# SCH_lucid_vr_proto_5_pcbs_2023-09-04.net
KiCad netlist of a schematic drawn in EasyEDA
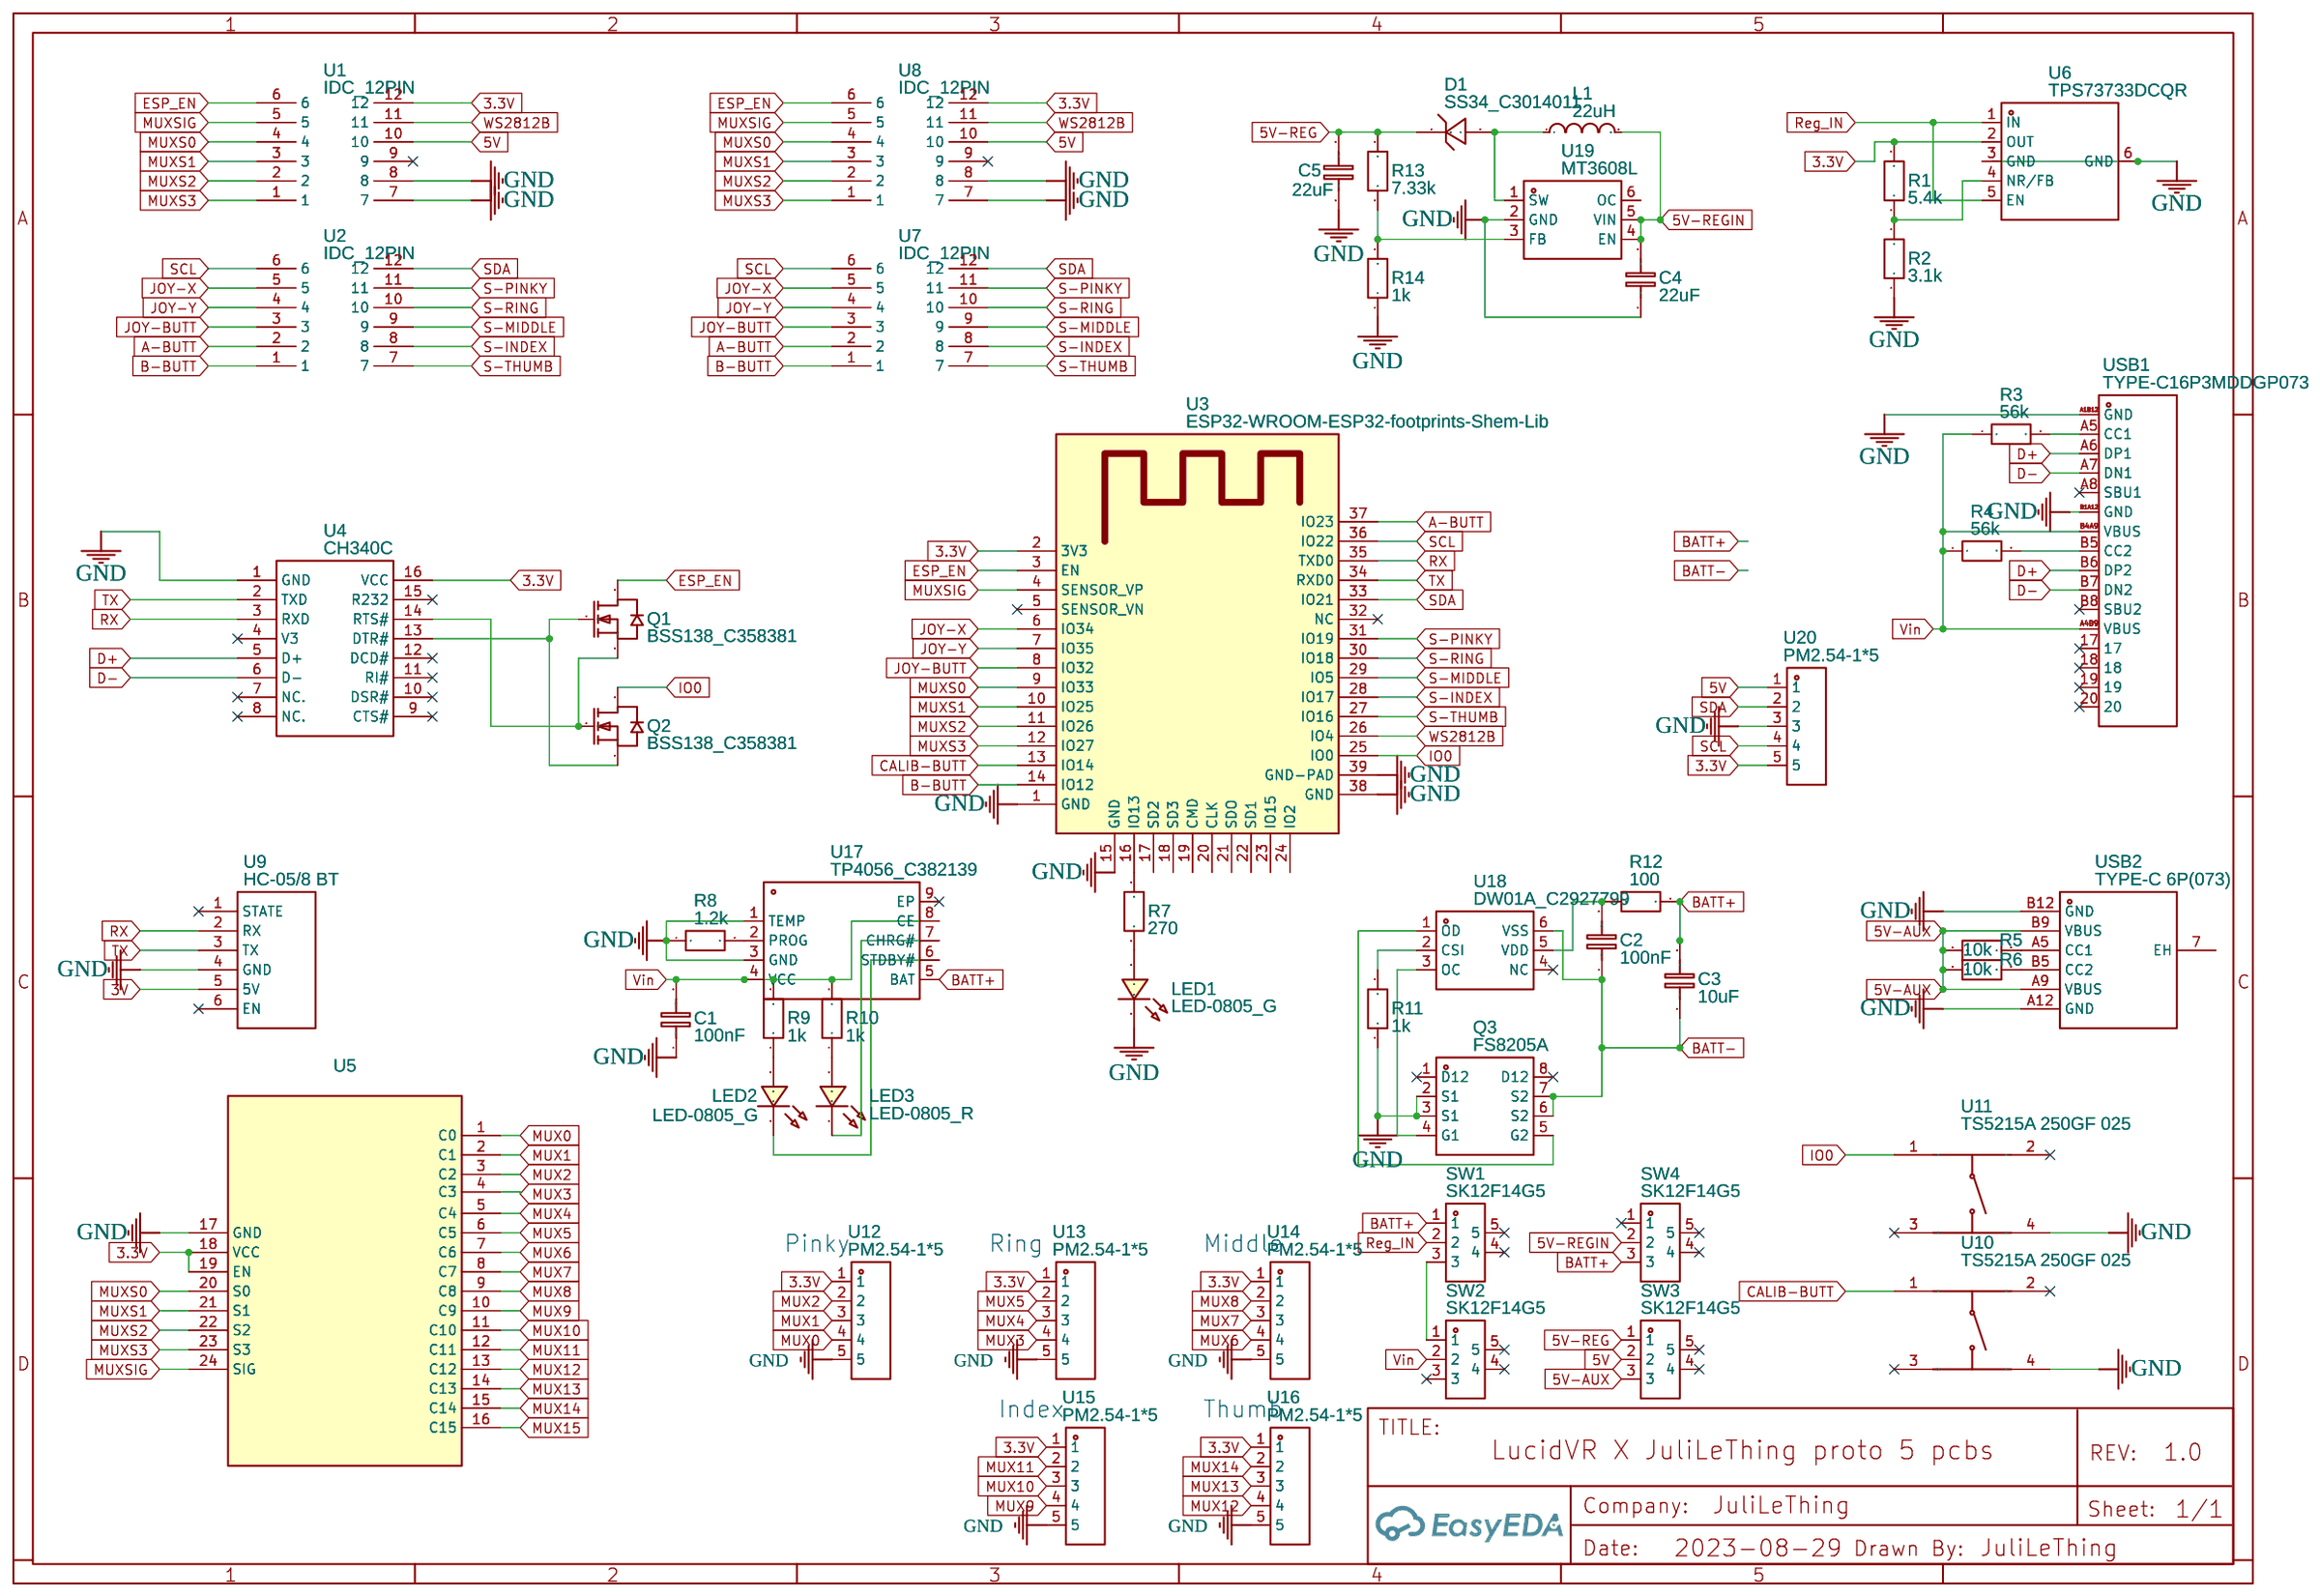
[diagram p0: schematic sheet]

(export (version "E")
  (design (tool "Eeschema 10.0.6"))
  (components
    (comp (ref "C1") (value "100nF") (libsource (lib "") (part "C_1206_EU_1")))
    (comp (ref "C2") (value "100nF") (libsource (lib "") (part "C_1206_EU_2")))
    (comp (ref "C3") (value "10uF") (libsource (lib "") (part "C_1206_EU_2")))
    (comp (ref "C4") (value "22uF") (libsource (lib "") (part "C_1206_EU")))
    (comp (ref "C5") (value "22uF") (libsource (lib "") (part "C_1206_EU")))
    (comp (ref "D1")
      (value "SS34_C3014011")
      (fields (field (name "Manufacturer Part") "SS34") (field (name "Manufacturer") "FOSAN(富信)"))
      (libsource (lib "") (part "SS34_C3014011"))
    )
    (comp (ref "L1") (value "22uH") (libsource (lib "") (part "L0805_US")))
    (comp (ref "LED1")
      (value "LED-0805_G")
      (fields (field (name "Manufacturer Part") "NCD0805G1") (field (name "Manufacturer") "国星光电"))
      (libsource (lib "") (part "LED-0805_G"))
    )
    (comp (ref "LED2")
      (value "LED-0805_G")
      (fields (field (name "Manufacturer Part") "NCD0805G1") (field (name "Manufacturer") "国星光电"))
      (libsource (lib "") (part "LED-0805_G"))
    )
    (comp (ref "LED3")
      (value "LED-0805_R")
      (fields
        (field (name "Manufacturer Part") "17-21SURC/S530-A3/TR8")
        (field (name "Manufacturer") "EVERLIGHT(台湾亿光)")
      )
      (libsource (lib "") (part "LED-0805_R"))
    )
    (comp (ref "Q1")
      (value "BSS138_C358381")
      (fields (field (name "Manufacturer Part") "BSS138") (field (name "Manufacturer") "BLUE ROCKET(蓝箭)"))
      (libsource (lib "") (part "BSS138_C358381"))
    )
    (comp (ref "Q2")
      (value "BSS138_C358381")
      (fields (field (name "Manufacturer Part") "BSS138") (field (name "Manufacturer") "BLUE ROCKET(蓝箭)"))
      (libsource (lib "") (part "BSS138_C358381"))
    )
    (comp (ref "Q3")
      (value "FS8205A")
      (fields (field (name "Manufacturer") "FORTUNE(富晶)"))
      (libsource (lib "") (part "FS8205A"))
    )
    (comp (ref "R1") (value "5.4k") (libsource (lib "") (part "R_1206_EU")))
    (comp (ref "R2") (value "3.1k") (libsource (lib "") (part "R_1206_EU")))
    (comp (ref "R3") (value "56k") (libsource (lib "") (part "R_1206_EU_1")))
    (comp (ref "R4") (value "56k") (libsource (lib "") (part "R_1206_EU_1")))
    (comp (ref "R5") (value "10k") (libsource (lib "") (part "R_1206_EU_1")))
    (comp (ref "R6") (value "10k") (libsource (lib "") (part "R_1206_EU_1")))
    (comp (ref "R7") (value "270") (libsource (lib "") (part "R_1206_EU_2")))
    (comp (ref "R8") (value "1.2k") (libsource (lib "") (part "R_1206_EU_1")))
    (comp (ref "R9") (value "1k") (libsource (lib "") (part "R_1206_EU")))
    (comp (ref "R10") (value "1k") (libsource (lib "") (part "R_1206_EU")))
    (comp (ref "R11") (value "1k") (libsource (lib "") (part "R_1206_EU")))
    (comp (ref "R12") (value "100") (libsource (lib "") (part "R_1206_EU_1")))
    (comp (ref "R13") (value "7.33k") (libsource (lib "") (part "R_1206_EU")))
    (comp (ref "R14") (value "1k") (libsource (lib "") (part "R_1206_EU")))
    (comp (ref "SW1")
      (value "SK12F14G5")
      (fields (field (name "Manufacturer") "SHOU HAN(首韩)"))
      (libsource (lib "") (part "SK12F14G5"))
    )
    (comp (ref "SW2")
      (value "SK12F14G5")
      (fields (field (name "Manufacturer") "SHOU HAN(首韩)"))
      (libsource (lib "") (part "SK12F14G5"))
    )
    (comp (ref "SW3")
      (value "SK12F14G5")
      (fields (field (name "Manufacturer") "SHOU HAN(首韩)"))
      (libsource (lib "") (part "SK12F14G5"))
    )
    (comp (ref "SW4")
      (value "SK12F14G5")
      (fields (field (name "Manufacturer") "SHOU HAN(首韩)"))
      (libsource (lib "") (part "SK12F14G5"))
    )
    (comp (ref "U1") (value "IDC_12PIN") (libsource (lib "") (part "IDC_12PIN")))
    (comp (ref "U2") (value "IDC_12PIN") (libsource (lib "") (part "IDC_12PIN")))
    (comp (ref "U3")
      (value "ESP32-WROOM-ESP32-footprints-Shem-Lib")
      (libsource (lib "") (part "ESP32-WROOM-ESP32-footprints-Shem-Lib"))
    )
    (comp (ref "U4")
      (value "CH340C")
      (fields (field (name "Manufacturer") "WCH(南京沁恒)"))
      (libsource (lib "") (part "CH340C"))
    )
    (comp (ref "U5") (value "NO") (libsource (lib "") (part "16x1_Mux_board_CD74HC4067")))
    (comp (ref "U6")
      (value "TPS73733DCQR")
      (fields (field (name "Manufacturer") "TI(德州仪器)"))
      (libsource (lib "") (part "TPS73733DCQR"))
    )
    (comp (ref "U7") (value "IDC_12PIN") (libsource (lib "") (part "IDC_12PIN")))
    (comp (ref "U8") (value "IDC_12PIN") (libsource (lib "") (part "IDC_12PIN")))
    (comp (ref "U9") (value "HC-05/8 BT") (libsource (lib "") (part "HC08 Bluetooth Module")))
    (comp (ref "U10")
      (value "TS5215A 250GF 025")
      (fields
        (field (name "Manufacturer Part") "TS5215A 250gf 025")
        (field (name "Manufacturer") "SHOU HAN(首韩)")
      )
      (libsource (lib "") (part "TS5215A 250GF 025"))
    )
    (comp (ref "U11")
      (value "TS5215A 250GF 025")
      (fields
        (field (name "Manufacturer Part") "TS5215A 250gf 025")
        (field (name "Manufacturer") "SHOU HAN(首韩)")
      )
      (libsource (lib "") (part "TS5215A 250GF 025"))
    )
    (comp (ref "U12")
      (value "PM2.54-1*5")
      (fields (field (name "Manufacturer") "ZHOURI(洲日)"))
      (libsource (lib "") (part "PM2.54-1*5"))
    )
    (comp (ref "U13")
      (value "PM2.54-1*5")
      (fields (field (name "Manufacturer") "ZHOURI(洲日)"))
      (libsource (lib "") (part "PM2.54-1*5"))
    )
    (comp (ref "U14")
      (value "PM2.54-1*5")
      (fields (field (name "Manufacturer") "ZHOURI(洲日)"))
      (libsource (lib "") (part "PM2.54-1*5"))
    )
    (comp (ref "U15")
      (value "PM2.54-1*5")
      (fields (field (name "Manufacturer") "ZHOURI(洲日)"))
      (libsource (lib "") (part "PM2.54-1*5"))
    )
    (comp (ref "U16")
      (value "PM2.54-1*5")
      (fields (field (name "Manufacturer") "ZHOURI(洲日)"))
      (libsource (lib "") (part "PM2.54-1*5"))
    )
    (comp (ref "U17")
      (value "TP4056_C382139")
      (fields (field (name "Manufacturer Part") "TP4056") (field (name "Manufacturer") "TPOWER(天源)"))
      (libsource (lib "") (part "TP4056_C382139"))
    )
    (comp (ref "U18")
      (value "DW01A_C2927799")
      (fields (field (name "Manufacturer Part") "DW01A") (field (name "Manufacturer") "YONGYUTAI(永裕泰)"))
      (libsource (lib "") (part "DW01A_C2927799"))
    )
    (comp (ref "U19")
      (value "MT3608L")
      (fields (field (name "Manufacturer") "西安航天民芯"))
      (libsource (lib "") (part "MT3608L"))
    )
    (comp (ref "U20")
      (value "PM2.54-1*5")
      (fields (field (name "Manufacturer") "ZHOURI(洲日)"))
      (libsource (lib "") (part "PM2.54-1*5"))
    )
    (comp (ref "USB1")
      (value "TYPE-C16P3MDDGP073")
      (fields (field (name "Manufacturer") "SHOU HAN(首韩)"))
      (libsource (lib "") (part "TYPE-C16P3MDDGP073"))
    )
    (comp (ref "USB2")
      (value "TYPE-C 6P(073)")
      (fields (field (name "Manufacturer") "SHOU HAN(首韩)"))
      (libsource (lib "") (part "TYPE-C 6P(073)"))
    )
  )
  (nets
    (net (code "1") (name "3.3V") (class "Default")
      (node (ref "R1") (pin "2") (pinfunction "2_2") (pintype "unspecified"))
      (node (ref "U1") (pin "12") (pinfunction "12_12") (pintype "unspecified"))
      (node (ref "U12") (pin "1") (pinfunction "1_1") (pintype "unspecified"))
      (node (ref "U13") (pin "1") (pinfunction "1_1") (pintype "unspecified"))
      (node (ref "U14") (pin "1") (pinfunction "1_1") (pintype "unspecified"))
      (node (ref "U15") (pin "1") (pinfunction "1_1") (pintype "unspecified"))
      (node (ref "U16") (pin "1") (pinfunction "1_1") (pintype "unspecified"))
      (node (ref "U20") (pin "5") (pinfunction "5_5") (pintype "unspecified"))
      (node (ref "U3") (pin "2") (pinfunction "3V3_2") (pintype "bidirectional"))
      (node (ref "U4") (pin "16") (pinfunction "VCC_16") (pintype "unspecified"))
      (node (ref "U5") (pin "18") (pinfunction "VCC_18") (pintype "unspecified"))
      (node (ref "U5") (pin "19") (pinfunction "EN_19") (pintype "unspecified"))
      (node (ref "U6") (pin "2") (pinfunction "OUT_2") (pintype "unspecified"))
      (node (ref "U8") (pin "12") (pinfunction "12_12") (pintype "unspecified"))
    )
    (net (code "2") (name "3V") (class "Default")
      (node (ref "U9") (pin "5") (pinfunction "5V_5") (pintype "unspecified"))
    )
    (net (code "3") (name "5V") (class "Default")
      (node (ref "SW3") (pin "2") (pinfunction "2_2") (pintype "unspecified"))
      (node (ref "U1") (pin "10") (pinfunction "10_10") (pintype "unspecified"))
      (node (ref "U20") (pin "1") (pinfunction "1_1") (pintype "unspecified"))
      (node (ref "U8") (pin "10") (pinfunction "10_10") (pintype "unspecified"))
    )
    (net (code "4") (name "5V-AUX") (class "Default")
      (node (ref "R5") (pin "1") (pinfunction "1_1") (pintype "unspecified"))
      (node (ref "R6") (pin "1") (pinfunction "1_1") (pintype "unspecified"))
      (node (ref "SW3") (pin "3") (pinfunction "3_3") (pintype "unspecified"))
      (node (ref "USB2") (pin "A9") (pinfunction "VBUS_A9") (pintype "unspecified"))
      (node (ref "USB2") (pin "B9") (pinfunction "VBUS_B9") (pintype "unspecified"))
    )
    (net (code "5") (name "5V-REG") (class "Default")
      (node (ref "C5") (pin "2") (pinfunction "2_2") (pintype "unspecified"))
      (node (ref "D1") (pin "1") (pinfunction "C_1") (pintype "unspecified"))
      (node (ref "R13") (pin "2") (pinfunction "2_2") (pintype "unspecified"))
      (node (ref "SW3") (pin "1") (pinfunction "1_1") (pintype "unspecified"))
    )
    (net (code "6") (name "5V-REGIN") (class "Default")
      (node (ref "C4") (pin "2") (pinfunction "2_2") (pintype "unspecified"))
      (node (ref "L1") (pin "2") (pinfunction "2_2") (pintype "unspecified"))
      (node (ref "SW4") (pin "2") (pinfunction "2_2") (pintype "unspecified"))
      (node (ref "U19") (pin "4") (pinfunction "EN_4") (pintype "unspecified"))
      (node (ref "U19") (pin "5") (pinfunction "VIN_5") (pintype "unspecified"))
    )
    (net (code "7") (name "A-BUTT") (class "Default")
      (node (ref "U2") (pin "2") (pinfunction "2_2") (pintype "unspecified"))
      (node (ref "U3") (pin "37") (pinfunction "IO23_37") (pintype "bidirectional"))
      (node (ref "U7") (pin "2") (pinfunction "2_2") (pintype "unspecified"))
    )
    (net (code "8") (name "B-BUTT") (class "Default")
      (node (ref "U2") (pin "1") (pinfunction "1_1") (pintype "unspecified"))
      (node (ref "U3") (pin "14") (pinfunction "IO12_14") (pintype "bidirectional"))
      (node (ref "U7") (pin "1") (pinfunction "1_1") (pintype "unspecified"))
    )
    (net (code "9") (name "BATT+") (class "Default")
      (node (ref "C3") (pin "2") (pinfunction "2_2") (pintype "unspecified"))
      (node (ref "R12") (pin "2") (pinfunction "2_2") (pintype "unspecified"))
      (node (ref "SW1") (pin "1") (pinfunction "1_1") (pintype "unspecified"))
      (node (ref "SW4") (pin "3") (pinfunction "3_3") (pintype "unspecified"))
      (node (ref "U17") (pin "5") (pinfunction "BAT_5") (pintype "unspecified"))
    )
    (net (code "10") (name "BATT-") (class "Default")
      (node (ref "C2") (pin "1") (pinfunction "1_1") (pintype "unspecified"))
      (node (ref "C3") (pin "1") (pinfunction "1_1") (pintype "unspecified"))
      (node (ref "Q3") (pin "6") (pinfunction "S2_6") (pintype "unspecified"))
      (node (ref "Q3") (pin "7") (pinfunction "S2_7") (pintype "unspecified"))
      (node (ref "U18") (pin "6") (pinfunction "VSS_6") (pintype "unspecified"))
    )
    (net (code "11") (name "CALIB-BUTT") (class "Default")
      (node (ref "U10") (pin "1") (pinfunction "1_1") (pintype "unspecified"))
      (node (ref "U3") (pin "13") (pinfunction "IO14_13") (pintype "bidirectional"))
    )
    (net (code "12") (name "D+") (class "Default")
      (node (ref "U4") (pin "5") (pinfunction "D+_5") (pintype "unspecified"))
      (node (ref "USB1") (pin "A6") (pinfunction "DP1_A6") (pintype "unspecified"))
      (node (ref "USB1") (pin "B6") (pinfunction "DP2_B6") (pintype "unspecified"))
    )
    (net (code "13") (name "D-") (class "Default")
      (node (ref "U4") (pin "6") (pinfunction "D-_6") (pintype "unspecified"))
      (node (ref "USB1") (pin "A7") (pinfunction "DN1_A7") (pintype "unspecified"))
      (node (ref "USB1") (pin "B7") (pinfunction "DN2_B7") (pintype "unspecified"))
    )
    (net (code "14") (name "ESP_EN") (class "Default")
      (node (ref "Q1") (pin "3") (pinfunction "D_3") (pintype "unspecified"))
      (node (ref "U1") (pin "6") (pinfunction "6_6") (pintype "unspecified"))
      (node (ref "U3") (pin "3") (pinfunction "EN_3") (pintype "input"))
      (node (ref "U8") (pin "6") (pinfunction "6_6") (pintype "unspecified"))
    )
    (net (code "15") (name "GND") (class "Default")
      (node (ref "C1") (pin "1") (pinfunction "1_1") (pintype "unspecified"))
      (node (ref "C4") (pin "1") (pinfunction "1_1") (pintype "unspecified"))
      (node (ref "C5") (pin "1") (pinfunction "1_1") (pintype "unspecified"))
      (node (ref "LED1") (pin "2") (pinfunction "2_2") (pintype "unspecified"))
      (node (ref "Q3") (pin "2") (pinfunction "S1_2") (pintype "unspecified"))
      (node (ref "Q3") (pin "3") (pinfunction "S1_3") (pintype "unspecified"))
      (node (ref "R11") (pin "1") (pinfunction "1_1") (pintype "unspecified"))
      (node (ref "R14") (pin "1") (pinfunction "1_1") (pintype "unspecified"))
      (node (ref "R2") (pin "1") (pinfunction "1_1") (pintype "unspecified"))
      (node (ref "R8") (pin "1") (pinfunction "1_1") (pintype "unspecified"))
      (node (ref "U1") (pin "7") (pinfunction "7_7") (pintype "unspecified"))
      (node (ref "U1") (pin "8") (pinfunction "8_8") (pintype "unspecified"))
      (node (ref "U10") (pin "4") (pinfunction "4_4") (pintype "unspecified"))
      (node (ref "U11") (pin "4") (pinfunction "4_4") (pintype "unspecified"))
      (node (ref "U12") (pin "5") (pinfunction "5_5") (pintype "unspecified"))
      (node (ref "U13") (pin "5") (pinfunction "5_5") (pintype "unspecified"))
      (node (ref "U14") (pin "5") (pinfunction "5_5") (pintype "unspecified"))
      (node (ref "U15") (pin "5") (pinfunction "5_5") (pintype "unspecified"))
      (node (ref "U16") (pin "5") (pinfunction "5_5") (pintype "unspecified"))
      (node (ref "U17") (pin "1") (pinfunction "TEMP_1") (pintype "unspecified"))
      (node (ref "U17") (pin "3") (pinfunction "GND_3") (pintype "unspecified"))
      (node (ref "U19") (pin "2") (pinfunction "GND_2") (pintype "unspecified"))
      (node (ref "U20") (pin "3") (pinfunction "3_3") (pintype "unspecified"))
      (node (ref "U3") (pin "1") (pinfunction "GND_1") (pintype "bidirectional"))
      (node (ref "U3") (pin "15") (pinfunction "GND_15") (pintype "bidirectional"))
      (node (ref "U3") (pin "38") (pinfunction "GND_38") (pintype "bidirectional"))
      (node (ref "U3") (pin "39") (pinfunction "GND-PAD_39") (pintype "bidirectional"))
      (node (ref "U4") (pin "1") (pinfunction "GND_1") (pintype "unspecified"))
      (node (ref "U5") (pin "17") (pinfunction "GND_17") (pintype "unspecified"))
      (node (ref "U6") (pin "6") (pinfunction "GND_6") (pintype "unspecified"))
      (node (ref "U8") (pin "7") (pinfunction "7_7") (pintype "unspecified"))
      (node (ref "U8") (pin "8") (pinfunction "8_8") (pintype "unspecified"))
      (node (ref "U9") (pin "4") (pinfunction "GND_4") (pintype "unspecified"))
      (node (ref "USB1") (pin "A1B12") (pinfunction "GND_A1B12") (pintype "unspecified"))
      (node (ref "USB1") (pin "B1A12") (pinfunction "GND_B1A12") (pintype "unspecified"))
      (node (ref "USB2") (pin "A12") (pinfunction "GND_A12") (pintype "unspecified"))
      (node (ref "USB2") (pin "B12") (pinfunction "GND_B12") (pintype "unspecified"))
    )
    (net (code "16") (name "IO0") (class "Default")
      (node (ref "Q2") (pin "3") (pinfunction "D_3") (pintype "unspecified"))
      (node (ref "U11") (pin "1") (pinfunction "1_1") (pintype "unspecified"))
      (node (ref "U3") (pin "25") (pinfunction "IO0_25") (pintype "bidirectional"))
    )
    (net (code "17") (name "JOY-BUTT") (class "Default")
      (node (ref "U2") (pin "3") (pinfunction "3_3") (pintype "unspecified"))
      (node (ref "U3") (pin "8") (pinfunction "IO32_8") (pintype "bidirectional"))
      (node (ref "U7") (pin "3") (pinfunction "3_3") (pintype "unspecified"))
    )
    (net (code "18") (name "JOY-X") (class "Default")
      (node (ref "U2") (pin "5") (pinfunction "5_5") (pintype "unspecified"))
      (node (ref "U3") (pin "6") (pinfunction "IO34_6") (pintype "bidirectional"))
      (node (ref "U7") (pin "5") (pinfunction "5_5") (pintype "unspecified"))
    )
    (net (code "19") (name "JOY-Y") (class "Default")
      (node (ref "U2") (pin "4") (pinfunction "4_4") (pintype "unspecified"))
      (node (ref "U3") (pin "7") (pinfunction "IO35_7") (pintype "bidirectional"))
      (node (ref "U7") (pin "4") (pinfunction "4_4") (pintype "unspecified"))
    )
    (net (code "20") (name "MUX0") (class "Default")
      (node (ref "U12") (pin "4") (pinfunction "4_4") (pintype "unspecified"))
      (node (ref "U5") (pin "1") (pinfunction "C0_1") (pintype "unspecified"))
    )
    (net (code "21") (name "MUX1") (class "Default")
      (node (ref "U12") (pin "3") (pinfunction "3_3") (pintype "unspecified"))
      (node (ref "U5") (pin "2") (pinfunction "C1_2") (pintype "unspecified"))
    )
    (net (code "22") (name "MUX2") (class "Default")
      (node (ref "U12") (pin "2") (pinfunction "2_2") (pintype "unspecified"))
      (node (ref "U5") (pin "3") (pinfunction "C2_3") (pintype "unspecified"))
    )
    (net (code "23") (name "MUX3") (class "Default")
      (node (ref "U13") (pin "4") (pinfunction "4_4") (pintype "unspecified"))
      (node (ref "U5") (pin "4") (pinfunction "C3_4") (pintype "unspecified"))
    )
    (net (code "24") (name "MUX4") (class "Default")
      (node (ref "U13") (pin "3") (pinfunction "3_3") (pintype "unspecified"))
      (node (ref "U5") (pin "5") (pinfunction "C4_5") (pintype "unspecified"))
    )
    (net (code "25") (name "MUX5") (class "Default")
      (node (ref "U13") (pin "2") (pinfunction "2_2") (pintype "unspecified"))
      (node (ref "U5") (pin "6") (pinfunction "C5_6") (pintype "unspecified"))
    )
    (net (code "26") (name "MUX6") (class "Default")
      (node (ref "U14") (pin "4") (pinfunction "4_4") (pintype "unspecified"))
      (node (ref "U5") (pin "7") (pinfunction "C6_7") (pintype "unspecified"))
    )
    (net (code "27") (name "MUX7") (class "Default")
      (node (ref "U14") (pin "3") (pinfunction "3_3") (pintype "unspecified"))
      (node (ref "U5") (pin "8") (pinfunction "C7_8") (pintype "unspecified"))
    )
    (net (code "28") (name "MUX8") (class "Default")
      (node (ref "U14") (pin "2") (pinfunction "2_2") (pintype "unspecified"))
      (node (ref "U5") (pin "9") (pinfunction "C8_9") (pintype "unspecified"))
    )
    (net (code "29") (name "MUX9") (class "Default")
      (node (ref "U15") (pin "4") (pinfunction "4_4") (pintype "unspecified"))
      (node (ref "U5") (pin "10") (pinfunction "C9_10") (pintype "unspecified"))
    )
    (net (code "30") (name "MUX10") (class "Default")
      (node (ref "U15") (pin "3") (pinfunction "3_3") (pintype "unspecified"))
      (node (ref "U5") (pin "11") (pinfunction "C10_11") (pintype "unspecified"))
    )
    (net (code "31") (name "MUX11") (class "Default")
      (node (ref "U15") (pin "2") (pinfunction "2_2") (pintype "unspecified"))
      (node (ref "U5") (pin "12") (pinfunction "C11_12") (pintype "unspecified"))
    )
    (net (code "32") (name "MUX12") (class "Default")
      (node (ref "U16") (pin "4") (pinfunction "4_4") (pintype "unspecified"))
      (node (ref "U5") (pin "13") (pinfunction "C12_13") (pintype "unspecified"))
    )
    (net (code "33") (name "MUX13") (class "Default")
      (node (ref "U16") (pin "3") (pinfunction "3_3") (pintype "unspecified"))
      (node (ref "U5") (pin "14") (pinfunction "C13_14") (pintype "unspecified"))
    )
    (net (code "34") (name "MUX14") (class "Default")
      (node (ref "U16") (pin "2") (pinfunction "2_2") (pintype "unspecified"))
      (node (ref "U5") (pin "15") (pinfunction "C14_15") (pintype "unspecified"))
    )
    (net (code "35") (name "MUX15") (class "Default")
      (node (ref "U5") (pin "16") (pinfunction "C15_16") (pintype "unspecified"))
    )
    (net (code "36") (name "MUXS0") (class "Default")
      (node (ref "U1") (pin "4") (pinfunction "4_4") (pintype "unspecified"))
      (node (ref "U3") (pin "9") (pinfunction "IO33_9") (pintype "bidirectional"))
      (node (ref "U5") (pin "20") (pinfunction "S0_20") (pintype "unspecified"))
      (node (ref "U8") (pin "4") (pinfunction "4_4") (pintype "unspecified"))
    )
    (net (code "37") (name "MUXS1") (class "Default")
      (node (ref "U1") (pin "3") (pinfunction "3_3") (pintype "unspecified"))
      (node (ref "U3") (pin "10") (pinfunction "IO25_10") (pintype "bidirectional"))
      (node (ref "U5") (pin "21") (pinfunction "S1_21") (pintype "unspecified"))
      (node (ref "U8") (pin "3") (pinfunction "3_3") (pintype "unspecified"))
    )
    (net (code "38") (name "MUXS2") (class "Default")
      (node (ref "U1") (pin "2") (pinfunction "2_2") (pintype "unspecified"))
      (node (ref "U3") (pin "11") (pinfunction "IO26_11") (pintype "bidirectional"))
      (node (ref "U5") (pin "22") (pinfunction "S2_22") (pintype "unspecified"))
      (node (ref "U8") (pin "2") (pinfunction "2_2") (pintype "unspecified"))
    )
    (net (code "39") (name "MUXS3") (class "Default")
      (node (ref "U1") (pin "1") (pinfunction "1_1") (pintype "unspecified"))
      (node (ref "U3") (pin "12") (pinfunction "IO27_12") (pintype "bidirectional"))
      (node (ref "U5") (pin "23") (pinfunction "S3_23") (pintype "unspecified"))
      (node (ref "U8") (pin "1") (pinfunction "1_1") (pintype "unspecified"))
    )
    (net (code "40") (name "MUXSIG") (class "Default")
      (node (ref "U1") (pin "5") (pinfunction "5_5") (pintype "unspecified"))
      (node (ref "U3") (pin "4") (pinfunction "SENSOR_VP_4") (pintype "input"))
      (node (ref "U5") (pin "24") (pinfunction "SIG_24") (pintype "unspecified"))
      (node (ref "U8") (pin "5") (pinfunction "5_5") (pintype "unspecified"))
    )
    (net (code "41") (name "Net-(D1-A)") (class "Default")
      (node (ref "D1") (pin "2") (pinfunction "A_2") (pintype "unspecified"))
      (node (ref "L1") (pin "1") (pinfunction "1_1") (pintype "unspecified"))
      (node (ref "U19") (pin "1") (pinfunction "SW_1") (pintype "unspecified"))
    )
    (net (code "42") (name "Net-(LED1-Pad1)") (class "Default")
      (node (ref "LED1") (pin "1") (pinfunction "1_1") (pintype "unspecified"))
      (node (ref "R7") (pin "2") (pinfunction "2_2") (pintype "unspecified"))
    )
    (net (code "43") (name "Net-(LED2-Pad1)") (class "Default")
      (node (ref "LED2") (pin "1") (pinfunction "1_1") (pintype "unspecified"))
      (node (ref "R9") (pin "1") (pinfunction "1_1") (pintype "unspecified"))
    )
    (net (code "44") (name "Net-(LED3-Pad1)") (class "Default")
      (node (ref "LED3") (pin "1") (pinfunction "1_1") (pintype "unspecified"))
      (node (ref "R10") (pin "1") (pinfunction "1_1") (pintype "unspecified"))
    )
    (net (code "45") (name "Net-(Q1-G)") (class "Default")
      (node (ref "Q1") (pin "1") (pinfunction "G_1") (pintype "unspecified"))
      (node (ref "Q2") (pin "2") (pinfunction "S_2") (pintype "unspecified"))
      (node (ref "U4") (pin "13") (pinfunction "DTR#_13") (pintype "unspecified"))
    )
    (net (code "46") (name "Net-(Q1-S)") (class "Default")
      (node (ref "Q1") (pin "2") (pinfunction "S_2") (pintype "unspecified"))
      (node (ref "Q2") (pin "1") (pinfunction "G_1") (pintype "unspecified"))
      (node (ref "U4") (pin "14") (pinfunction "RTS#_14") (pintype "unspecified"))
    )
    (net (code "47") (name "Net-(Q3-G1)") (class "Default")
      (node (ref "Q3") (pin "4") (pinfunction "G1_4") (pintype "unspecified"))
      (node (ref "U18") (pin "3") (pinfunction "OC_3") (pintype "unspecified"))
    )
    (net (code "48") (name "Net-(Q3-G2)") (class "Default")
      (node (ref "Q3") (pin "5") (pinfunction "G2_5") (pintype "unspecified"))
      (node (ref "U18") (pin "1") (pinfunction "OD_1") (pintype "unspecified"))
    )
    (net (code "49") (name "Net-(SW1-Pad3)") (class "Default")
      (node (ref "SW1") (pin "3") (pinfunction "3_3") (pintype "unspecified"))
      (node (ref "SW2") (pin "1") (pinfunction "1_1") (pintype "unspecified"))
    )
    (net (code "50") (name "Net-(U3-IO13)") (class "Default")
      (node (ref "R7") (pin "1") (pinfunction "1_1") (pintype "unspecified"))
      (node (ref "U3") (pin "16") (pinfunction "IO13_16") (pintype "bidirectional"))
    )
    (net (code "51") (name "Net-(U6-NR{slash}FB)") (class "Default")
      (node (ref "R1") (pin "1") (pinfunction "1_1") (pintype "unspecified"))
      (node (ref "R2") (pin "2") (pinfunction "2_2") (pintype "unspecified"))
      (node (ref "U6") (pin "4") (pinfunction "NR/FB_4") (pintype "unspecified"))
    )
    (net (code "52") (name "Net-(U17-CHRG#)") (class "Default")
      (node (ref "LED3") (pin "2") (pinfunction "2_2") (pintype "unspecified"))
      (node (ref "U17") (pin "7") (pinfunction "CHRG#_7") (pintype "unspecified"))
    )
    (net (code "53") (name "Net-(U17-PROG)") (class "Default")
      (node (ref "R8") (pin "2") (pinfunction "2_2") (pintype "unspecified"))
      (node (ref "U17") (pin "2") (pinfunction "PROG_2") (pintype "unspecified"))
    )
    (net (code "54") (name "Net-(U17-STDBY#)") (class "Default")
      (node (ref "LED2") (pin "2") (pinfunction "2_2") (pintype "unspecified"))
      (node (ref "U17") (pin "6") (pinfunction "STDBY#_6") (pintype "unspecified"))
    )
    (net (code "55") (name "Net-(U18-CSI)") (class "Default")
      (node (ref "R11") (pin "2") (pinfunction "2_2") (pintype "unspecified"))
      (node (ref "U18") (pin "2") (pinfunction "CSI_2") (pintype "unspecified"))
    )
    (net (code "56") (name "Net-(U18-VDD)") (class "Default")
      (node (ref "C2") (pin "2") (pinfunction "2_2") (pintype "unspecified"))
      (node (ref "R12") (pin "1") (pinfunction "1_1") (pintype "unspecified"))
      (node (ref "U18") (pin "5") (pinfunction "VDD_5") (pintype "unspecified"))
    )
    (net (code "57") (name "Net-(U19-FB)") (class "Default")
      (node (ref "R13") (pin "1") (pinfunction "1_1") (pintype "unspecified"))
      (node (ref "R14") (pin "2") (pinfunction "2_2") (pintype "unspecified"))
      (node (ref "U19") (pin "3") (pinfunction "FB_3") (pintype "unspecified"))
    )
    (net (code "58") (name "Net-(USB1-CC1)") (class "Default")
      (node (ref "R3") (pin "2") (pinfunction "2_2") (pintype "unspecified"))
      (node (ref "USB1") (pin "A5") (pinfunction "CC1_A5") (pintype "unspecified"))
    )
    (net (code "59") (name "Net-(USB1-CC2)") (class "Default")
      (node (ref "R4") (pin "2") (pinfunction "2_2") (pintype "unspecified"))
      (node (ref "USB1") (pin "B5") (pinfunction "CC2_B5") (pintype "unspecified"))
    )
    (net (code "60") (name "Net-(USB2-CC1)") (class "Default")
      (node (ref "R5") (pin "2") (pinfunction "2_2") (pintype "unspecified"))
      (node (ref "USB2") (pin "A5") (pinfunction "CC1_A5") (pintype "unspecified"))
    )
    (net (code "61") (name "Net-(USB2-CC2)") (class "Default")
      (node (ref "R6") (pin "2") (pinfunction "2_2") (pintype "unspecified"))
      (node (ref "USB2") (pin "B5") (pinfunction "CC2_B5") (pintype "unspecified"))
    )
    (net (code "62") (name "RX") (class "Default")
      (node (ref "U3") (pin "35") (pinfunction "TXD0_35") (pintype "bidirectional"))
      (node (ref "U4") (pin "3") (pinfunction "RXD_3") (pintype "unspecified"))
      (node (ref "U9") (pin "2") (pinfunction "RX_2") (pintype "unspecified"))
    )
    (net (code "63") (name "Reg_IN") (class "Default")
      (node (ref "SW1") (pin "2") (pinfunction "2_2") (pintype "unspecified"))
      (node (ref "U6") (pin "1") (pinfunction "IN_1") (pintype "unspecified"))
      (node (ref "U6") (pin "5") (pinfunction "EN_5") (pintype "unspecified"))
    )
    (net (code "64") (name "S-INDEX") (class "Default")
      (node (ref "U2") (pin "8") (pinfunction "8_8") (pintype "unspecified"))
      (node (ref "U3") (pin "28") (pinfunction "IO17_28") (pintype "bidirectional"))
      (node (ref "U7") (pin "8") (pinfunction "8_8") (pintype "unspecified"))
    )
    (net (code "65") (name "S-MIDDLE") (class "Default")
      (node (ref "U2") (pin "9") (pinfunction "9_9") (pintype "unspecified"))
      (node (ref "U3") (pin "29") (pinfunction "IO5_29") (pintype "bidirectional"))
      (node (ref "U7") (pin "9") (pinfunction "9_9") (pintype "unspecified"))
    )
    (net (code "66") (name "S-PINKY") (class "Default")
      (node (ref "U2") (pin "11") (pinfunction "11_11") (pintype "unspecified"))
      (node (ref "U3") (pin "31") (pinfunction "IO19_31") (pintype "bidirectional"))
      (node (ref "U7") (pin "11") (pinfunction "11_11") (pintype "unspecified"))
    )
    (net (code "67") (name "S-RING") (class "Default")
      (node (ref "U2") (pin "10") (pinfunction "10_10") (pintype "unspecified"))
      (node (ref "U3") (pin "30") (pinfunction "IO18_30") (pintype "input"))
      (node (ref "U7") (pin "10") (pinfunction "10_10") (pintype "unspecified"))
    )
    (net (code "68") (name "S-THUMB") (class "Default")
      (node (ref "U2") (pin "7") (pinfunction "7_7") (pintype "unspecified"))
      (node (ref "U3") (pin "27") (pinfunction "IO16_27") (pintype "bidirectional"))
      (node (ref "U7") (pin "7") (pinfunction "7_7") (pintype "unspecified"))
    )
    (net (code "69") (name "SCL") (class "Default")
      (node (ref "U2") (pin "6") (pinfunction "6_6") (pintype "unspecified"))
      (node (ref "U20") (pin "4") (pinfunction "4_4") (pintype "unspecified"))
      (node (ref "U3") (pin "36") (pinfunction "IO22_36") (pintype "bidirectional"))
      (node (ref "U7") (pin "6") (pinfunction "6_6") (pintype "unspecified"))
    )
    (net (code "70") (name "SDA") (class "Default")
      (node (ref "U2") (pin "12") (pinfunction "12_12") (pintype "unspecified"))
      (node (ref "U20") (pin "2") (pinfunction "2_2") (pintype "unspecified"))
      (node (ref "U3") (pin "33") (pinfunction "IO21_33") (pintype "bidirectional"))
      (node (ref "U7") (pin "12") (pinfunction "12_12") (pintype "unspecified"))
    )
    (net (code "71") (name "TX") (class "Default")
      (node (ref "U3") (pin "34") (pinfunction "RXD0_34") (pintype "bidirectional"))
      (node (ref "U4") (pin "2") (pinfunction "TXD_2") (pintype "unspecified"))
      (node (ref "U9") (pin "3") (pinfunction "TX_3") (pintype "unspecified"))
    )
    (net (code "72") (name "Vin") (class "Default")
      (node (ref "C1") (pin "2") (pinfunction "2_2") (pintype "unspecified"))
      (node (ref "R10") (pin "2") (pinfunction "2_2") (pintype "unspecified"))
      (node (ref "R3") (pin "1") (pinfunction "1_1") (pintype "unspecified"))
      (node (ref "R4") (pin "1") (pinfunction "1_1") (pintype "unspecified"))
      (node (ref "R9") (pin "2") (pinfunction "2_2") (pintype "unspecified"))
      (node (ref "SW2") (pin "2") (pinfunction "2_2") (pintype "unspecified"))
      (node (ref "U17") (pin "4") (pinfunction "VCC_4") (pintype "unspecified"))
      (node (ref "U17") (pin "8") (pinfunction "CE_8") (pintype "unspecified"))
      (node (ref "USB1") (pin "A4B9") (pinfunction "VBUS_A4B9") (pintype "unspecified"))
      (node (ref "USB1") (pin "B4A9") (pinfunction "VBUS_B4A9") (pintype "unspecified"))
    )
    (net (code "73") (name "WS2812B") (class "Default")
      (node (ref "U1") (pin "11") (pinfunction "11_11") (pintype "unspecified"))
      (node (ref "U3") (pin "26") (pinfunction "IO4_26") (pintype "input"))
      (node (ref "U8") (pin "11") (pinfunction "11_11") (pintype "unspecified"))
    )
    (net (code "74") (name "unconnected-(Q3-D12-Pad1)") (class "Default")
      (node (ref "Q3") (pin "1") (pinfunction "D12_1") (pintype "unspecified+no_connect"))
    )
    (net (code "75") (name "unconnected-(Q3-D12-Pad8)") (class "Default")
      (node (ref "Q3") (pin "8") (pinfunction "D12_8") (pintype "unspecified+no_connect"))
    )
    (net (code "76") (name "unconnected-(SW1-Pad4)") (class "Default")
      (node (ref "SW1") (pin "4") (pinfunction "4_4") (pintype "unspecified+no_connect"))
    )
    (net (code "77") (name "unconnected-(SW1-Pad5)") (class "Default")
      (node (ref "SW1") (pin "5") (pinfunction "5_5") (pintype "unspecified+no_connect"))
    )
    (net (code "78") (name "unconnected-(SW2-Pad3)") (class "Default")
      (node (ref "SW2") (pin "3") (pinfunction "3_3") (pintype "unspecified+no_connect"))
    )
    (net (code "79") (name "unconnected-(SW2-Pad4)") (class "Default")
      (node (ref "SW2") (pin "4") (pinfunction "4_4") (pintype "unspecified+no_connect"))
    )
    (net (code "80") (name "unconnected-(SW2-Pad5)") (class "Default")
      (node (ref "SW2") (pin "5") (pinfunction "5_5") (pintype "unspecified+no_connect"))
    )
    (net (code "81") (name "unconnected-(SW3-Pad4)") (class "Default")
      (node (ref "SW3") (pin "4") (pinfunction "4_4") (pintype "unspecified+no_connect"))
    )
    (net (code "82") (name "unconnected-(SW3-Pad5)") (class "Default")
      (node (ref "SW3") (pin "5") (pinfunction "5_5") (pintype "unspecified+no_connect"))
    )
    (net (code "83") (name "unconnected-(SW4-Pad1)") (class "Default")
      (node (ref "SW4") (pin "1") (pinfunction "1_1") (pintype "unspecified+no_connect"))
    )
    (net (code "84") (name "unconnected-(SW4-Pad4)") (class "Default")
      (node (ref "SW4") (pin "4") (pinfunction "4_4") (pintype "unspecified+no_connect"))
    )
    (net (code "85") (name "unconnected-(SW4-Pad5)") (class "Default")
      (node (ref "SW4") (pin "5") (pinfunction "5_5") (pintype "unspecified+no_connect"))
    )
    (net (code "86") (name "unconnected-(U1-Pad9)") (class "Default")
      (node (ref "U1") (pin "9") (pinfunction "9_9") (pintype "unspecified+no_connect"))
    )
    (net (code "87") (name "unconnected-(U3-CLK-Pad20)") (class "Default")
      (node (ref "U3") (pin "20") (pinfunction "CLK_20") (pintype "input"))
    )
    (net (code "88") (name "unconnected-(U3-CMD-Pad19)") (class "Default")
      (node (ref "U3") (pin "19") (pinfunction "CMD_19") (pintype "bidirectional"))
    )
    (net (code "89") (name "unconnected-(U3-IO2-Pad24)") (class "Default")
      (node (ref "U3") (pin "24") (pinfunction "IO2_24") (pintype "bidirectional"))
    )
    (net (code "90") (name "unconnected-(U3-IO15-Pad23)") (class "Default")
      (node (ref "U3") (pin "23") (pinfunction "IO15_23") (pintype "bidirectional"))
    )
    (net (code "91") (name "unconnected-(U3-NC-Pad32)") (class "Default")
      (node (ref "U3") (pin "32") (pinfunction "NC_32") (pintype "bidirectional+no_connect"))
    )
    (net (code "92") (name "unconnected-(U3-SD1-Pad22)") (class "Default")
      (node (ref "U3") (pin "22") (pinfunction "SD1_22") (pintype "bidirectional"))
    )
    (net (code "93") (name "unconnected-(U3-SD2-Pad17)") (class "Default")
      (node (ref "U3") (pin "17") (pinfunction "SD2_17") (pintype "bidirectional"))
    )
    (net (code "94") (name "unconnected-(U3-SD3-Pad18)") (class "Default")
      (node (ref "U3") (pin "18") (pinfunction "SD3_18") (pintype "bidirectional"))
    )
    (net (code "95") (name "unconnected-(U3-SDO-Pad21)") (class "Default")
      (node (ref "U3") (pin "21") (pinfunction "SDO_21") (pintype "bidirectional"))
    )
    (net (code "96") (name "unconnected-(U3-SENSOR_VN-Pad5)") (class "Default")
      (node (ref "U3") (pin "5") (pinfunction "SENSOR_VN_5") (pintype "input+no_connect"))
    )
    (net (code "97") (name "unconnected-(U4-CTS#-Pad9)") (class "Default")
      (node (ref "U4") (pin "9") (pinfunction "CTS#_9") (pintype "unspecified+no_connect"))
    )
    (net (code "98") (name "unconnected-(U4-DCD#-Pad12)") (class "Default")
      (node (ref "U4") (pin "12") (pinfunction "DCD#_12") (pintype "unspecified+no_connect"))
    )
    (net (code "99") (name "unconnected-(U4-DSR#-Pad10)") (class "Default")
      (node (ref "U4") (pin "10") (pinfunction "DSR#_10") (pintype "unspecified+no_connect"))
    )
    (net (code "100") (name "unconnected-(U4-NC.-Pad7)") (class "Default")
      (node (ref "U4") (pin "7") (pinfunction "NC._7") (pintype "unspecified+no_connect"))
    )
    (net (code "101") (name "unconnected-(U4-NC.-Pad8)") (class "Default")
      (node (ref "U4") (pin "8") (pinfunction "NC._8") (pintype "unspecified+no_connect"))
    )
    (net (code "102") (name "unconnected-(U4-R232-Pad15)") (class "Default")
      (node (ref "U4") (pin "15") (pinfunction "R232_15") (pintype "unspecified+no_connect"))
    )
    (net (code "103") (name "unconnected-(U4-RI#-Pad11)") (class "Default")
      (node (ref "U4") (pin "11") (pinfunction "RI#_11") (pintype "unspecified+no_connect"))
    )
    (net (code "104") (name "unconnected-(U4-V3-Pad4)") (class "Default")
      (node (ref "U4") (pin "4") (pinfunction "V3_4") (pintype "unspecified+no_connect"))
    )
    (net (code "105") (name "unconnected-(U6-GND-Pad3)") (class "Default")
      (node (ref "U6") (pin "3") (pinfunction "GND_3") (pintype "unspecified"))
    )
    (net (code "106") (name "unconnected-(U8-Pad9)") (class "Default")
      (node (ref "U8") (pin "9") (pinfunction "9_9") (pintype "unspecified+no_connect"))
    )
    (net (code "107") (name "unconnected-(U9-EN-Pad6)") (class "Default")
      (node (ref "U9") (pin "6") (pinfunction "EN_6") (pintype "unspecified+no_connect"))
    )
    (net (code "108") (name "unconnected-(U9-STATE-Pad1)") (class "Default")
      (node (ref "U9") (pin "1") (pinfunction "STATE_1") (pintype "unspecified+no_connect"))
    )
    (net (code "109") (name "unconnected-(U10-Pad2)") (class "Default")
      (node (ref "U10") (pin "2") (pinfunction "2_2") (pintype "unspecified+no_connect"))
    )
    (net (code "110") (name "unconnected-(U10-Pad3)") (class "Default")
      (node (ref "U10") (pin "3") (pinfunction "3_3") (pintype "unspecified+no_connect"))
    )
    (net (code "111") (name "unconnected-(U11-Pad2)") (class "Default")
      (node (ref "U11") (pin "2") (pinfunction "2_2") (pintype "unspecified+no_connect"))
    )
    (net (code "112") (name "unconnected-(U11-Pad3)") (class "Default")
      (node (ref "U11") (pin "3") (pinfunction "3_3") (pintype "unspecified+no_connect"))
    )
    (net (code "113") (name "unconnected-(U17-EP-Pad9)") (class "Default")
      (node (ref "U17") (pin "9") (pinfunction "EP_9") (pintype "unspecified+no_connect"))
    )
    (net (code "114") (name "unconnected-(U18-NC-Pad4)") (class "Default")
      (node (ref "U18") (pin "4") (pinfunction "NC_4") (pintype "unspecified+no_connect"))
    )
    (net (code "115") (name "unconnected-(U19-OC-Pad6)") (class "Default")
      (node (ref "U19") (pin "6") (pinfunction "OC_6") (pintype "unspecified"))
    )
    (net (code "116") (name "unconnected-(USB1-Pad17)") (class "Default")
      (node (ref "USB1") (pin "17") (pinfunction "17_17") (pintype "unspecified+no_connect"))
    )
    (net (code "117") (name "unconnected-(USB1-Pad18)") (class "Default")
      (node (ref "USB1") (pin "18") (pinfunction "18_18") (pintype "unspecified+no_connect"))
    )
    (net (code "118") (name "unconnected-(USB1-Pad19)") (class "Default")
      (node (ref "USB1") (pin "19") (pinfunction "19_19") (pintype "unspecified+no_connect"))
    )
    (net (code "119") (name "unconnected-(USB1-Pad20)") (class "Default")
      (node (ref "USB1") (pin "20") (pinfunction "20_20") (pintype "unspecified+no_connect"))
    )
    (net (code "120") (name "unconnected-(USB1-SBU1-PadA8)") (class "Default")
      (node (ref "USB1") (pin "A8") (pinfunction "SBU1_A8") (pintype "unspecified+no_connect"))
    )
    (net (code "121") (name "unconnected-(USB1-SBU2-PadB8)") (class "Default")
      (node (ref "USB1") (pin "B8") (pinfunction "SBU2_B8") (pintype "unspecified+no_connect"))
    )
    (net (code "122") (name "unconnected-(USB2-EH-Pad7)") (class "Default")
      (node (ref "USB2") (pin "7") (pinfunction "EH_7") (pintype "unspecified"))
    )
  )
)
